# Mic_Schematic.net
KiCad netlist of a schematic drawn in Altium Designer
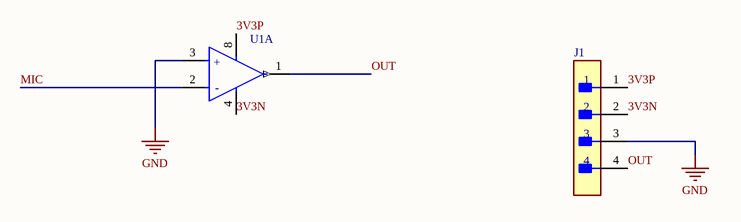
[diagram p0: Mic_Schematic.SchDoc]

(export (version "E")
  (design (tool "Eeschema 10.0.6"))
  (components
    (comp (ref "J1")
      (value "HDR")
      (footprint "FP-MTLW-104-05-G-S-185-MFG")
      (description "CONN HEADER VERT 4POS 2.54MM")
      (libsource (lib "Altium Content Vault") (part "299a8cea1bdcbc3624fe62c390fa72c"))
    )
    (comp (ref "U1")
      (value "LM358DR2G")
      (footprint "FP-751-07-IPC_C")
      (description "IC OPAMP GP 2 CIRCUIT 8SOIC")
      (libsource (lib "Altium Content Vault") (part "992a6607d1d88c80ee6b45e5ba6cb1b"))
    )
  )
  (nets
    (net (code "1") (name "/3V3N") (class "Default")
      (node (ref "J1") (pin "2") (pinfunction "2_2") (pintype "passive"))
      (node (ref "U1") (pin "4") (pinfunction "VEE/GND_4") (pintype "power_in"))
    )
    (net (code "2") (name "/3V3P") (class "Default")
      (node (ref "J1") (pin "1") (pinfunction "1_1") (pintype "passive"))
      (node (ref "U1") (pin "8") (pinfunction "VCC_8") (pintype "power_in"))
    )
    (net (code "3") (name "/MIC") (class "Default")
      (node (ref "U1") (pin "2") (pinfunction "INPUT_A-_2") (pintype "tri_state"))
    )
    (net (code "4") (name "/OUT") (class "Default")
      (node (ref "J1") (pin "4") (pinfunction "4_4") (pintype "passive"))
      (node (ref "U1") (pin "1") (pinfunction "OUTPUT_A_1") (pintype "output"))
    )
    (net (code "5") (name "GND") (class "Default")
      (node (ref "J1") (pin "3") (pinfunction "3_3") (pintype "passive"))
      (node (ref "U1") (pin "3") (pinfunction "INPUT_A+_3") (pintype "tri_state"))
    )
  )
)
